# C2_Servos.net
KiCad netlist of a schematic drawn in EAGLE
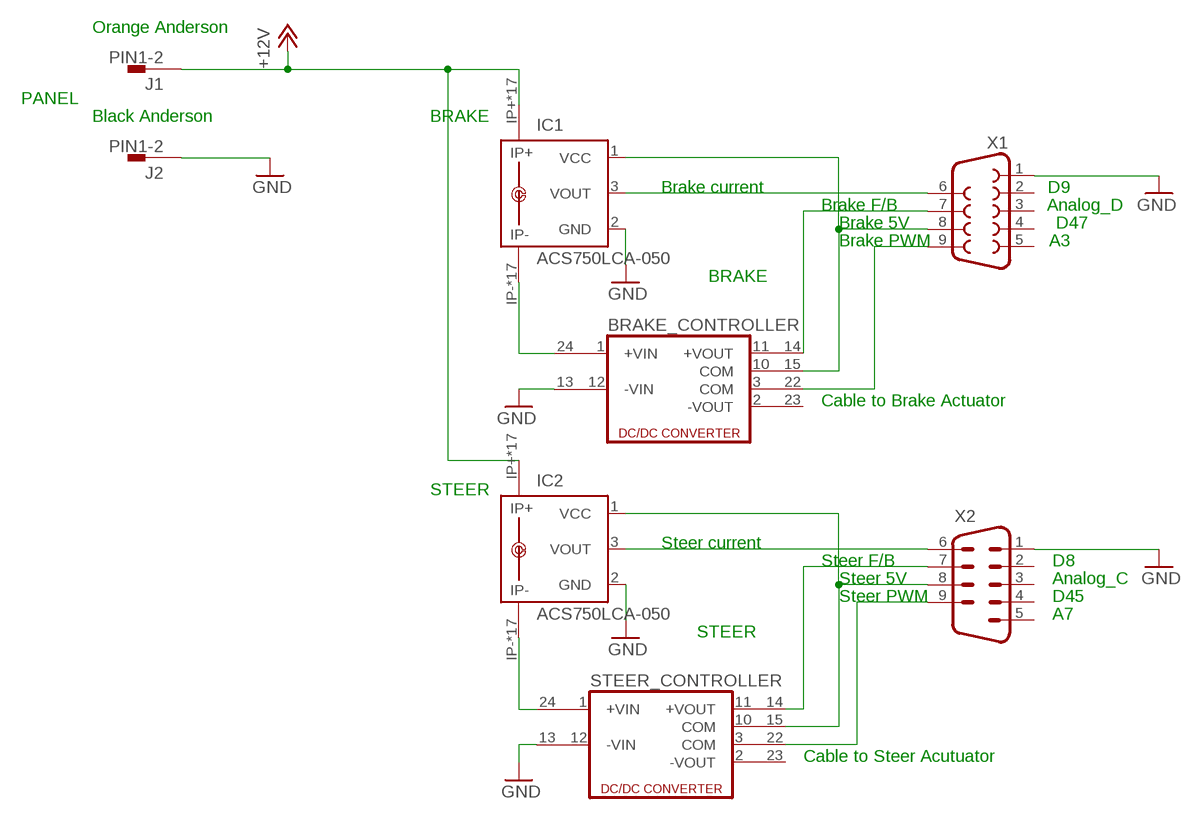
[diagram p0: schematic, sheet 1]

(export (version "E")
  (design (tool "Eeschema 10.0.6"))
  (components
    (comp (ref "BRAKE_CONTROLLER")
      (value "DCW2C")
      (footprint "eagle-import:DCW")
      (libsource (lib "eagle-import") (part "DCW2C"))
    )
    (comp (ref "IC1")
      (value "ACS750LCA-050")
      (footprint "eagle-import:ACS75050")
      (fields (field (name "MF") "ALLEGRO MICROSYSTEMS, INC."))
      (libsource (lib "eagle-import") (part "ACS750CA-050L"))
    )
    (comp (ref "IC2")
      (value "ACS750LCA-050")
      (footprint "eagle-import:ACS75050")
      (fields (field (name "MF") "ALLEGRO MICROSYSTEMS, INC."))
      (libsource (lib "eagle-import") (part "ACS750CA-050L"))
    )
    (comp (ref "J1")
      (value "PIN1-2")
      (footprint "eagle-import:62221")
      (fields (field (name "MF") "TYCO ELECTRONICS") (field (name "MPN") "62221-1"))
      (libsource (lib "eagle-import") (part "PIN1-2"))
    )
    (comp (ref "J2")
      (value "PIN1-2")
      (footprint "eagle-import:62221")
      (fields (field (name "MF") "TYCO ELECTRONICS") (field (name "MPN") "62221-1"))
      (libsource (lib "eagle-import") (part "PIN1-2"))
    )
    (comp (ref "STEER_CONTROLLER")
      (value "DCW2C")
      (footprint "eagle-import:DCW")
      (libsource (lib "eagle-import") (part "DCW2C"))
    )
    (comp (ref "X1")
      (value "F09H")
      (footprint "eagle-import:F09H")
      (libsource (lib "eagle-import") (part "F09H"))
    )
    (comp (ref "X2")
      (value "M09-182")
      (footprint "eagle-import:182-009-MALE")
      (libsource (lib "eagle-import") (part "M09-182"))
    )
  )
  (nets
    (net (code "1") (name "+12V") (class "Default")
      (node (ref "IC1") (pin "IP+") (pinfunction "IP+_IP+") (pintype "passive"))
      (node (ref "IC1") (pin "IP+@10") (pinfunction "IP+_IP+@10") (pintype "passive"))
      (node (ref "IC1") (pin "IP+@11") (pinfunction "IP+_IP+@11") (pintype "passive"))
      (node (ref "IC1") (pin "IP+@12") (pinfunction "IP+_IP+@12") (pintype "passive"))
      (node (ref "IC1") (pin "IP+@13") (pinfunction "IP+_IP+@13") (pintype "passive"))
      (node (ref "IC1") (pin "IP+@14") (pinfunction "IP+_IP+@14") (pintype "passive"))
      (node (ref "IC1") (pin "IP+@15") (pinfunction "IP+_IP+@15") (pintype "passive"))
      (node (ref "IC1") (pin "IP+@16") (pinfunction "IP+_IP+@16") (pintype "passive"))
      (node (ref "IC1") (pin "IP+@17") (pinfunction "IP+_IP+@17") (pintype "passive"))
      (node (ref "IC1") (pin "IP+@2") (pinfunction "IP+_IP+@2") (pintype "passive"))
      (node (ref "IC1") (pin "IP+@3") (pinfunction "IP+_IP+@3") (pintype "passive"))
      (node (ref "IC1") (pin "IP+@4") (pinfunction "IP+_IP+@4") (pintype "passive"))
      (node (ref "IC1") (pin "IP+@5") (pinfunction "IP+_IP+@5") (pintype "passive"))
      (node (ref "IC1") (pin "IP+@6") (pinfunction "IP+_IP+@6") (pintype "passive"))
      (node (ref "IC1") (pin "IP+@7") (pinfunction "IP+_IP+@7") (pintype "passive"))
      (node (ref "IC1") (pin "IP+@8") (pinfunction "IP+_IP+@8") (pintype "passive"))
      (node (ref "IC1") (pin "IP+@9") (pinfunction "IP+_IP+@9") (pintype "passive"))
      (node (ref "IC2") (pin "IP+") (pinfunction "IP+_IP+") (pintype "passive"))
      (node (ref "IC2") (pin "IP+@10") (pinfunction "IP+_IP+@10") (pintype "passive"))
      (node (ref "IC2") (pin "IP+@11") (pinfunction "IP+_IP+@11") (pintype "passive"))
      (node (ref "IC2") (pin "IP+@12") (pinfunction "IP+_IP+@12") (pintype "passive"))
      (node (ref "IC2") (pin "IP+@13") (pinfunction "IP+_IP+@13") (pintype "passive"))
      (node (ref "IC2") (pin "IP+@14") (pinfunction "IP+_IP+@14") (pintype "passive"))
      (node (ref "IC2") (pin "IP+@15") (pinfunction "IP+_IP+@15") (pintype "passive"))
      (node (ref "IC2") (pin "IP+@16") (pinfunction "IP+_IP+@16") (pintype "passive"))
      (node (ref "IC2") (pin "IP+@17") (pinfunction "IP+_IP+@17") (pintype "passive"))
      (node (ref "IC2") (pin "IP+@2") (pinfunction "IP+_IP+@2") (pintype "passive"))
      (node (ref "IC2") (pin "IP+@3") (pinfunction "IP+_IP+@3") (pintype "passive"))
      (node (ref "IC2") (pin "IP+@4") (pinfunction "IP+_IP+@4") (pintype "passive"))
      (node (ref "IC2") (pin "IP+@5") (pinfunction "IP+_IP+@5") (pintype "passive"))
      (node (ref "IC2") (pin "IP+@6") (pinfunction "IP+_IP+@6") (pintype "passive"))
      (node (ref "IC2") (pin "IP+@7") (pinfunction "IP+_IP+@7") (pintype "passive"))
      (node (ref "IC2") (pin "IP+@8") (pinfunction "IP+_IP+@8") (pintype "passive"))
      (node (ref "IC2") (pin "IP+@9") (pinfunction "IP+_IP+@9") (pintype "passive"))
      (node (ref "J1") (pin "1") (pinfunction "1_1") (pintype "passive"))
    )
    (net (code "2") (name "GND") (class "Default")
      (node (ref "BRAKE_CONTROLLER") (pin "13") (pinfunction "-VIN1_13") (pintype "passive"))
      (node (ref "IC1") (pin "2") (pinfunction "GND_2") (pintype "power_in"))
      (node (ref "IC2") (pin "2") (pinfunction "GND_2") (pintype "power_in"))
      (node (ref "J2") (pin "1") (pinfunction "1_1") (pintype "passive"))
      (node (ref "STEER_CONTROLLER") (pin "13") (pinfunction "-VIN1_13") (pintype "passive"))
      (node (ref "X1") (pin "1") (pinfunction "1_1") (pintype "passive"))
      (node (ref "X2") (pin "1") (pinfunction "1_1") (pintype "passive"))
    )
    (net (code "3") (name "Net-(BRAKE_CONTROLLER-+VIN1)") (class "Default")
      (node (ref "BRAKE_CONTROLLER") (pin "24") (pinfunction "+VIN1_24") (pintype "passive"))
      (node (ref "IC1") (pin "IP-") (pinfunction "IP-_IP-") (pintype "passive"))
      (node (ref "IC1") (pin "IP-@10") (pinfunction "IP-_IP-@10") (pintype "passive"))
      (node (ref "IC1") (pin "IP-@11") (pinfunction "IP-_IP-@11") (pintype "passive"))
      (node (ref "IC1") (pin "IP-@12") (pinfunction "IP-_IP-@12") (pintype "passive"))
      (node (ref "IC1") (pin "IP-@13") (pinfunction "IP-_IP-@13") (pintype "passive"))
      (node (ref "IC1") (pin "IP-@14") (pinfunction "IP-_IP-@14") (pintype "passive"))
      (node (ref "IC1") (pin "IP-@15") (pinfunction "IP-_IP-@15") (pintype "passive"))
      (node (ref "IC1") (pin "IP-@16") (pinfunction "IP-_IP-@16") (pintype "passive"))
      (node (ref "IC1") (pin "IP-@17") (pinfunction "IP-_IP-@17") (pintype "passive"))
      (node (ref "IC1") (pin "IP-@2") (pinfunction "IP-_IP-@2") (pintype "passive"))
      (node (ref "IC1") (pin "IP-@3") (pinfunction "IP-_IP-@3") (pintype "passive"))
      (node (ref "IC1") (pin "IP-@4") (pinfunction "IP-_IP-@4") (pintype "passive"))
      (node (ref "IC1") (pin "IP-@5") (pinfunction "IP-_IP-@5") (pintype "passive"))
      (node (ref "IC1") (pin "IP-@6") (pinfunction "IP-_IP-@6") (pintype "passive"))
      (node (ref "IC1") (pin "IP-@7") (pinfunction "IP-_IP-@7") (pintype "passive"))
      (node (ref "IC1") (pin "IP-@8") (pinfunction "IP-_IP-@8") (pintype "passive"))
      (node (ref "IC1") (pin "IP-@9") (pinfunction "IP-_IP-@9") (pintype "passive"))
    )
    (net (code "4") (name "Net-(BRAKE_CONTROLLER-+VOUT1)") (class "Default")
      (node (ref "BRAKE_CONTROLLER") (pin "14") (pinfunction "+VOUT1_14") (pintype "passive"))
      (node (ref "X1") (pin "7") (pinfunction "7_7") (pintype "passive"))
    )
    (net (code "5") (name "Net-(BRAKE_CONTROLLER-COM1)") (class "Default")
      (node (ref "BRAKE_CONTROLLER") (pin "15") (pinfunction "COM1_15") (pintype "passive"))
      (node (ref "IC1") (pin "1") (pinfunction "VCC_1") (pintype "power_in"))
      (node (ref "X1") (pin "8") (pinfunction "8_8") (pintype "passive"))
    )
    (net (code "6") (name "Net-(BRAKE_CONTROLLER-COM2)") (class "Default")
      (node (ref "BRAKE_CONTROLLER") (pin "22") (pinfunction "COM2_22") (pintype "passive"))
      (node (ref "X1") (pin "9") (pinfunction "9_9") (pintype "passive"))
    )
    (net (code "7") (name "Net-(IC1-VOUT)") (class "Default")
      (node (ref "IC1") (pin "3") (pinfunction "VOUT_3") (pintype "output"))
      (node (ref "X1") (pin "6") (pinfunction "6_6") (pintype "passive"))
    )
    (net (code "8") (name "Net-(IC2-VCC)") (class "Default")
      (node (ref "IC2") (pin "1") (pinfunction "VCC_1") (pintype "power_in"))
      (node (ref "STEER_CONTROLLER") (pin "15") (pinfunction "COM1_15") (pintype "passive"))
      (node (ref "X2") (pin "8") (pinfunction "8_8") (pintype "passive"))
    )
    (net (code "9") (name "Net-(IC2-VOUT)") (class "Default")
      (node (ref "IC2") (pin "3") (pinfunction "VOUT_3") (pintype "output"))
      (node (ref "X2") (pin "6") (pinfunction "6_6") (pintype "passive"))
    )
    (net (code "10") (name "Net-(STEER_CONTROLLER-+VIN1)") (class "Default")
      (node (ref "IC2") (pin "IP-") (pinfunction "IP-_IP-") (pintype "passive"))
      (node (ref "IC2") (pin "IP-@10") (pinfunction "IP-_IP-@10") (pintype "passive"))
      (node (ref "IC2") (pin "IP-@11") (pinfunction "IP-_IP-@11") (pintype "passive"))
      (node (ref "IC2") (pin "IP-@12") (pinfunction "IP-_IP-@12") (pintype "passive"))
      (node (ref "IC2") (pin "IP-@13") (pinfunction "IP-_IP-@13") (pintype "passive"))
      (node (ref "IC2") (pin "IP-@14") (pinfunction "IP-_IP-@14") (pintype "passive"))
      (node (ref "IC2") (pin "IP-@15") (pinfunction "IP-_IP-@15") (pintype "passive"))
      (node (ref "IC2") (pin "IP-@16") (pinfunction "IP-_IP-@16") (pintype "passive"))
      (node (ref "IC2") (pin "IP-@17") (pinfunction "IP-_IP-@17") (pintype "passive"))
      (node (ref "IC2") (pin "IP-@2") (pinfunction "IP-_IP-@2") (pintype "passive"))
      (node (ref "IC2") (pin "IP-@3") (pinfunction "IP-_IP-@3") (pintype "passive"))
      (node (ref "IC2") (pin "IP-@4") (pinfunction "IP-_IP-@4") (pintype "passive"))
      (node (ref "IC2") (pin "IP-@5") (pinfunction "IP-_IP-@5") (pintype "passive"))
      (node (ref "IC2") (pin "IP-@6") (pinfunction "IP-_IP-@6") (pintype "passive"))
      (node (ref "IC2") (pin "IP-@7") (pinfunction "IP-_IP-@7") (pintype "passive"))
      (node (ref "IC2") (pin "IP-@8") (pinfunction "IP-_IP-@8") (pintype "passive"))
      (node (ref "IC2") (pin "IP-@9") (pinfunction "IP-_IP-@9") (pintype "passive"))
      (node (ref "STEER_CONTROLLER") (pin "24") (pinfunction "+VIN1_24") (pintype "passive"))
    )
    (net (code "11") (name "Net-(STEER_CONTROLLER-+VOUT1)") (class "Default")
      (node (ref "STEER_CONTROLLER") (pin "14") (pinfunction "+VOUT1_14") (pintype "passive"))
      (node (ref "X2") (pin "7") (pinfunction "7_7") (pintype "passive"))
    )
    (net (code "12") (name "Net-(STEER_CONTROLLER-COM2)") (class "Default")
      (node (ref "STEER_CONTROLLER") (pin "22") (pinfunction "COM2_22") (pintype "passive"))
      (node (ref "X2") (pin "9") (pinfunction "9_9") (pintype "passive"))
    )
    (net (code "13") (name "unconnected-(BRAKE_CONTROLLER-+VIN-Pad1)") (class "Default")
      (node (ref "BRAKE_CONTROLLER") (pin "1") (pinfunction "+VIN_1") (pintype "passive"))
    )
    (net (code "14") (name "unconnected-(BRAKE_CONTROLLER-+VOUT-Pad11)") (class "Default")
      (node (ref "BRAKE_CONTROLLER") (pin "11") (pinfunction "+VOUT_11") (pintype "passive"))
    )
    (net (code "15") (name "unconnected-(BRAKE_CONTROLLER--VIN-Pad12)") (class "Default")
      (node (ref "BRAKE_CONTROLLER") (pin "12") (pinfunction "-VIN_12") (pintype "passive"))
    )
    (net (code "16") (name "unconnected-(BRAKE_CONTROLLER--VOUT-Pad2)") (class "Default")
      (node (ref "BRAKE_CONTROLLER") (pin "2") (pinfunction "-VOUT_2") (pintype "passive"))
    )
    (net (code "17") (name "unconnected-(BRAKE_CONTROLLER--VOUT1-Pad23)") (class "Default")
      (node (ref "BRAKE_CONTROLLER") (pin "23") (pinfunction "-VOUT1_23") (pintype "passive"))
    )
    (net (code "18") (name "unconnected-(BRAKE_CONTROLLER-COM-Pad3)") (class "Default")
      (node (ref "BRAKE_CONTROLLER") (pin "3") (pinfunction "COM_3") (pintype "passive"))
    )
    (net (code "19") (name "unconnected-(BRAKE_CONTROLLER-COM-Pad10)") (class "Default")
      (node (ref "BRAKE_CONTROLLER") (pin "10") (pinfunction "COM_10") (pintype "passive"))
    )
    (net (code "20") (name "unconnected-(STEER_CONTROLLER-+VIN-Pad1)") (class "Default")
      (node (ref "STEER_CONTROLLER") (pin "1") (pinfunction "+VIN_1") (pintype "passive"))
    )
    (net (code "21") (name "unconnected-(STEER_CONTROLLER-+VOUT-Pad11)") (class "Default")
      (node (ref "STEER_CONTROLLER") (pin "11") (pinfunction "+VOUT_11") (pintype "passive"))
    )
    (net (code "22") (name "unconnected-(STEER_CONTROLLER--VIN-Pad12)") (class "Default")
      (node (ref "STEER_CONTROLLER") (pin "12") (pinfunction "-VIN_12") (pintype "passive"))
    )
    (net (code "23") (name "unconnected-(STEER_CONTROLLER--VOUT-Pad2)") (class "Default")
      (node (ref "STEER_CONTROLLER") (pin "2") (pinfunction "-VOUT_2") (pintype "passive"))
    )
    (net (code "24") (name "unconnected-(STEER_CONTROLLER--VOUT1-Pad23)") (class "Default")
      (node (ref "STEER_CONTROLLER") (pin "23") (pinfunction "-VOUT1_23") (pintype "passive"))
    )
    (net (code "25") (name "unconnected-(STEER_CONTROLLER-COM-Pad3)") (class "Default")
      (node (ref "STEER_CONTROLLER") (pin "3") (pinfunction "COM_3") (pintype "passive"))
    )
    (net (code "26") (name "unconnected-(STEER_CONTROLLER-COM-Pad10)") (class "Default")
      (node (ref "STEER_CONTROLLER") (pin "10") (pinfunction "COM_10") (pintype "passive"))
    )
    (net (code "27") (name "unconnected-(X1-Pad2)") (class "Default")
      (node (ref "X1") (pin "2") (pinfunction "2_2") (pintype "passive"))
    )
    (net (code "28") (name "unconnected-(X1-Pad3)") (class "Default")
      (node (ref "X1") (pin "3") (pinfunction "3_3") (pintype "passive"))
    )
    (net (code "29") (name "unconnected-(X1-Pad4)") (class "Default")
      (node (ref "X1") (pin "4") (pinfunction "4_4") (pintype "passive"))
    )
    (net (code "30") (name "unconnected-(X1-Pad5)") (class "Default")
      (node (ref "X1") (pin "5") (pinfunction "5_5") (pintype "passive"))
    )
    (net (code "31") (name "unconnected-(X2-Pad2)") (class "Default")
      (node (ref "X2") (pin "2") (pinfunction "2_2") (pintype "passive"))
    )
    (net (code "32") (name "unconnected-(X2-Pad3)") (class "Default")
      (node (ref "X2") (pin "3") (pinfunction "3_3") (pintype "passive"))
    )
    (net (code "33") (name "unconnected-(X2-Pad4)") (class "Default")
      (node (ref "X2") (pin "4") (pinfunction "4_4") (pintype "passive"))
    )
    (net (code "34") (name "unconnected-(X2-Pad5)") (class "Default")
      (node (ref "X2") (pin "5") (pinfunction "5_5") (pintype "passive"))
    )
  )
)
